# ArduinoFIO.net
KiCad netlist of a schematic drawn in Altium Designer
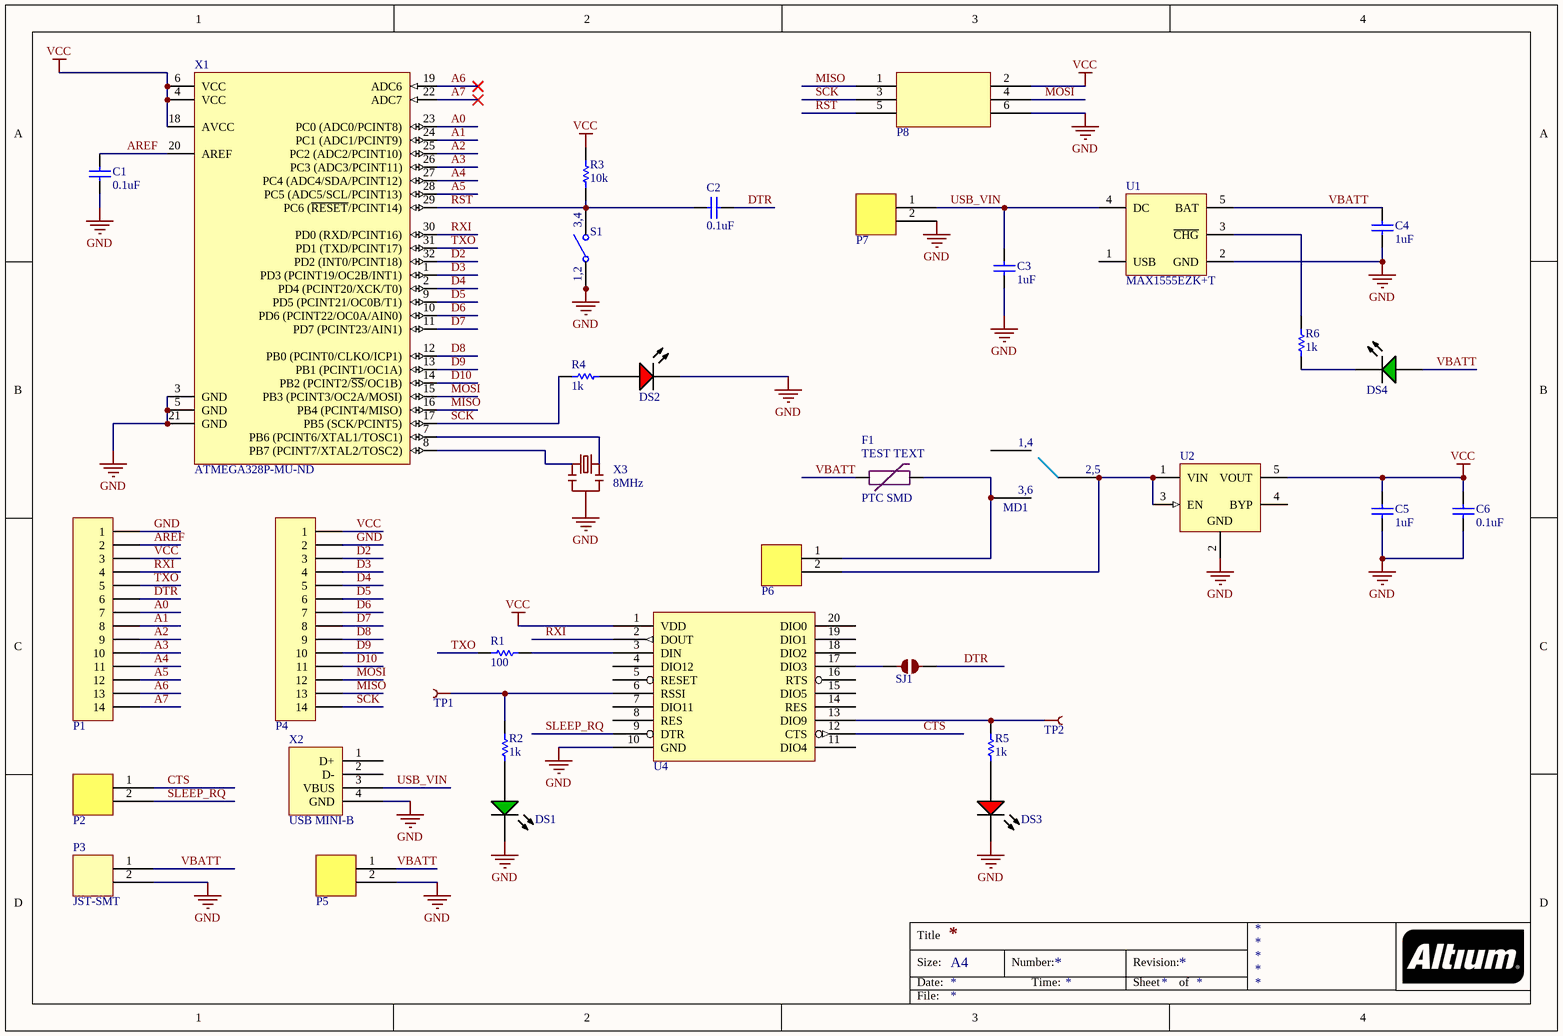
[diagram p0: ArduinoFIO.SchDoc]

(export (version "E")
  (design (tool "Eeschema 10.0.6"))
  (components
    (comp (ref "C1")
      (value "0.1uF")
      (footprint "Main PCB Library:0402")
      (description "CAP CER 0.1UF 50V 10% X7R 0402")
      (fields
        (field (name "MANUFACTURER") "TDK Corporation")
        (field (name "MANUFACTURER PART NUMBER") "C1005X7R1H104K050BB")
      )
      (libsource (lib "Main SCH Library") (part "C1005X7R1H104K050BB"))
    )
    (comp (ref "C2")
      (value "0.1uF")
      (footprint "Main PCB Library:0402")
      (description "CAP CER 0.1UF 50V 10% X7R 0402")
      (fields
        (field (name "MANUFACTURER") "TDK Corporation")
        (field (name "MANUFACTURER PART NUMBER") "C1005X7R1H104K050BB")
      )
      (libsource (lib "Main SCH Library") (part "C1005X7R1H104K050BB"))
    )
    (comp (ref "C3")
      (value "1uF")
      (footprint "Main PCB Library:0402")
      (description "CAP CER 1UF 6.3V 10% X5R 0402")
      (fields
        (field (name "MANUFACTURER") "Murata Electronics North America")
        (field (name "MANUFACTURER PART NUMBER") "GRM155R60J105KE19D")
      )
      (libsource (lib "Main SCH Library") (part "GRM155R60J105KE19D"))
    )
    (comp (ref "C4")
      (value "1uF")
      (footprint "Main PCB Library:0402")
      (description "CAP CER 1UF 6.3V 10% X5R 0402")
      (fields
        (field (name "MANUFACTURER") "Murata Electronics North America")
        (field (name "MANUFACTURER PART NUMBER") "GRM155R60J105KE19D")
      )
      (libsource (lib "Main SCH Library") (part "GRM155R60J105KE19D"))
    )
    (comp (ref "C5")
      (value "1uF")
      (footprint "Main PCB Library:0402")
      (description "CAP CER 1UF 6.3V 10% X5R 0402")
      (fields
        (field (name "MANUFACTURER") "Murata Electronics North America")
        (field (name "MANUFACTURER PART NUMBER") "GRM155R60J105KE19D")
      )
      (libsource (lib "Main SCH Library") (part "GRM155R60J105KE19D"))
    )
    (comp (ref "C6")
      (value "0.1uF")
      (footprint "Main PCB Library:0402")
      (description "CAP CER 0.1UF 50V 10% X7R 0402")
      (fields
        (field (name "MANUFACTURER") "TDK Corporation")
        (field (name "MANUFACTURER PART NUMBER") "C1005X7R1H104K050BB")
      )
      (libsource (lib "Main SCH Library") (part "C1005X7R1H104K050BB"))
    )
    (comp (ref "DS1")
      (value "LTST-C191KGKT")
      (footprint "Main PCB Library:KING-LED0603-25-GREEN_V")
      (description "LED GREEN CLEAR THIN 0603 SMD")
      (fields (field (name "MANUFACTURER") "Lite-On Inc."))
      (libsource (lib "Main SCH Library") (part "LTST-C191KGKT"))
    )
    (comp (ref "DS2")
      (value "LTST-C191KRKT")
      (footprint "Main PCB Library:KING-LED0603-25-RED_V")
      (description "LED SUPER RED CLR THIN 0603 SMD")
      (fields (field (name "MANUFACTURER") "Lite-On Inc."))
      (libsource (lib "Main SCH Library") (part "LTST-C191KRKT"))
    )
    (comp (ref "DS3")
      (value "LTST-C191KRKT")
      (footprint "Main PCB Library:KING-LED0603-25-RED_V")
      (description "LED SUPER RED CLR THIN 0603 SMD")
      (fields (field (name "MANUFACTURER") "Lite-On Inc."))
      (libsource (lib "Main SCH Library") (part "LTST-C191KRKT"))
    )
    (comp (ref "DS4")
      (value "LTST-C191KGKT")
      (footprint "Main PCB Library:KING-LED0603-25-GREEN_V")
      (description "LED GREEN CLEAR THIN 0603 SMD")
      (fields (field (name "MANUFACTURER") "Lite-On Inc."))
      (libsource (lib "Main SCH Library") (part "LTST-C191KGKT"))
    )
    (comp (ref "F1")
      (value "PTC SMD")
      (footprint "PTC-1206")
      (description "PTC RESTTBLE 0.10A 60V CHIP 1206")
      (fields
        (field (name "MANUFACTURER") "Bel Fuse Inc.")
        (field (name "MANUFACTURER PART NUMBER") "0ZCJ0010FF2E")
      )
      (libsource (lib "Main SCH Library") (part "0ZCJ0010FF2E"))
    )
    (comp (ref "MD1")
      (value "AYZ0202AGRLC")
      (footprint "Main PCB Library:DPDT SMD")
      (description "SWITCH SLIDE DPDT 100MA 12V")
      (fields (field (name "MANUFACTURER") "C&K Components"))
      (libsource (lib "Main SCH Library") (part "AYZ0202AGRLC"))
    )
    (comp (ref "P1")
      (value "95278-101A14LF")
      (footprint "Main PCB Library:1X14")
      (description "BERGSTIK Header 14POS .100\" DR SMT")
      (fields (field (name "MANUFACTURER") "FCI"))
      (libsource (lib "Main SCH Library") (part "95278-101A14LF"))
    )
    (comp (ref "P2")
      (value "961102-6404-AR")
      (footprint "Main PCB Library:1X02")
      (description "CONN HEADER VERT SGL 2POS GOLD")
      (fields (field (name "MANUFACTURER") "3M"))
      (libsource (lib "Main SCH Library") (part "961102-6404-AR"))
    )
    (comp (ref "P3")
      (value "JST-SMT")
      (footprint "S2B-PH")
      (description "CONN HEADER PH SIDE 2POS 2MM SMD")
      (fields
        (field (name "MANUFACTURER") "JST Sales America Inc.")
        (field (name "MANUFACTURER PART NUMBER") "S2B-PH-SM4-TB(LF)(SN)")
      )
      (libsource (lib "Main SCH Library") (part "S2B-PH-SM4-TB(LF)(SN)"))
    )
    (comp (ref "P4")
      (value "95278-101A14LF")
      (footprint "Main PCB Library:1X14")
      (description "BERGSTIK Header 14POS .100\" DR SMT")
      (fields (field (name "MANUFACTURER") "FCI"))
      (libsource (lib "Main SCH Library") (part "95278-101A14LF"))
    )
    (comp (ref "P5")
      (value "961102-6404-AR")
      (footprint "Main PCB Library:1X02")
      (description "CONN HEADER VERT SGL 2POS GOLD")
      (fields (field (name "MANUFACTURER") "3M"))
      (libsource (lib "Main SCH Library") (part "961102-6404-AR"))
    )
    (comp (ref "P6")
      (value "961102-6404-AR")
      (footprint "Main PCB Library:1X02")
      (description "CONN HEADER VERT SGL 2POS GOLD")
      (fields (field (name "MANUFACTURER") "3M"))
      (libsource (lib "Main SCH Library") (part "961102-6404-AR"))
    )
    (comp (ref "P7")
      (value "961102-6404-AR")
      (footprint "Main PCB Library:1X02")
      (description "CONN HEADER VERT SGL 2POS GOLD")
      (fields (field (name "MANUFACTURER") "3M"))
      (libsource (lib "Main SCH Library") (part "961102-6404-AR"))
    )
    (comp (ref "P8")
      (value "M20-9980346")
      (footprint "Main PCB Library:2X3")
      (description "DIL VERTICAL PC TAIL PIN HEADER")
      (fields (field (name "MANUFACTURER") "Harwin Inc."))
      (libsource (lib "Main SCH Library") (part "M20-9980346"))
    )
    (comp (ref "R1")
      (value "100")
      (footprint "Main PCB Library:J1-0603")
      (description "RES SMD 100 OHM 1% 1/10W 0603")
      (fields
        (field (name "MANUFACTURER") "Yageo")
        (field (name "MANUFACTURER PART NUMBER") "RC0603FR-07100RL")
      )
      (libsource (lib "Main SCH Library") (part "RC0603FR-07100RL"))
    )
    (comp (ref "R2")
      (value "1k")
      (footprint "Main PCB Library:J1-0603")
      (description "RES SMD 1K OHM 5% 1/10W 0603")
      (fields
        (field (name "MANUFACTURER") "Yageo")
        (field (name "MANUFACTURER PART NUMBER") "RC0603JR-071KL")
      )
      (libsource (lib "Main SCH Library") (part "RC0603JR-071KL"))
    )
    (comp (ref "R3")
      (value "10k")
      (footprint "Main PCB Library:J1-0603")
      (description "RES SMD 10K OHM 1% 1/10W 0603")
      (fields
        (field (name "MANUFACTURER") "Panasonic Electronic Components")
        (field (name "MANUFACTURER PART NUMBER") "ERJ-3EKF1002V")
      )
      (libsource (lib "Main SCH Library") (part "ERJ-3EKF1002V"))
    )
    (comp (ref "R4")
      (value "1k")
      (footprint "Main PCB Library:J1-0603")
      (description "RES SMD 1K OHM 5% 1/10W 0603")
      (fields
        (field (name "MANUFACTURER") "Yageo")
        (field (name "MANUFACTURER PART NUMBER") "RC0603JR-071KL")
      )
      (libsource (lib "Main SCH Library") (part "RC0603JR-071KL"))
    )
    (comp (ref "R5")
      (value "1k")
      (footprint "Main PCB Library:J1-0603")
      (description "RES SMD 1K OHM 5% 1/10W 0603")
      (fields
        (field (name "MANUFACTURER") "Yageo")
        (field (name "MANUFACTURER PART NUMBER") "RC0603JR-071KL")
      )
      (libsource (lib "Main SCH Library") (part "RC0603JR-071KL"))
    )
    (comp (ref "R6")
      (value "1k")
      (footprint "Main PCB Library:J1-0603")
      (description "RES SMD 1K OHM 5% 1/10W 0603")
      (fields
        (field (name "MANUFACTURER") "Yageo")
        (field (name "MANUFACTURER PART NUMBER") "RC0603JR-071KL")
      )
      (libsource (lib "Main SCH Library") (part "RC0603JR-071KL"))
    )
    (comp (ref "S1")
      (value "PTS645SH50SMTR92 LFS")
      (footprint "Main PCB Library:TACTILE SWITCH SMD")
      (description "SWITCH TACTILE SPST-NO 0.05A 12V")
      (fields (field (name "MANUFACTURER") "C&K Components"))
      (libsource (lib "Main SCH Library") (part "PTS645SH50SMTR92 LFS"))
    )
    (comp (ref "SJ1")
      (value "SOLDERJUMPERNC")
      (footprint "Main PCB Library:SJ_2S")
      (description "=SupplierDescription")
      (libsource (lib "Main SCH Library") (part "SOLDERJUMPERNC"))
    )
    (comp (ref "TP1")
      (value "TEST-POINT3X5")
      (footprint "Main PCB Library:PAD.03X.05")
      (description "=SupplierDescription")
      (libsource (lib "Main SCH Library") (part "TEST-POINT3X5"))
    )
    (comp (ref "TP2")
      (value "TEST-POINT3X5")
      (footprint "Main PCB Library:PAD.03X.05")
      (description "=SupplierDescription")
      (libsource (lib "") (part "TEST-POINT3X5_1"))
    )
    (comp (ref "U1")
      (value "MAX1555EZK+T")
      (footprint "Main PCB Library:SOT23-5")
      (description "IC BATT CHRGR LI+ 1CELL SOT23-5")
      (fields (field (name "MANUFACTURER") "Maxim Integrated"))
      (libsource (lib "Main SCH Library") (part "MAX1555EZK+T"))
    )
    (comp (ref "U2")
      (value "CAT6219-330TDGT3")
      (footprint "Main PCB Library:SOT23-5")
      (description "IC REG LDO 3.3V 0.5A TSOT23-5")
      (fields (field (name "MANUFACTURER") "ON Semiconductor"))
      (libsource (lib "Main SCH Library") (part "CAT6219-330TDGT3"))
    )
    (comp (ref "U4")
      (value "XB24-API-001")
      (footprint "Main PCB Library:XBEE-SMD")
      (description "MOD XBEE 802.15.4 1MW W/PCB ANT")
      (fields (field (name "MANUFACTURER") "Digi International"))
      (libsource (lib "Main SCH Library") (part "XB24-API-001"))
    )
    (comp (ref "X1")
      (value "ATMEGA328P-MU")
      (footprint "Main PCB Library:32A_N")
      (description "IC MCU 8BIT 32KB FLASH 32QFN")
      (fields
        (field (name "MANUFACTURER") "Atmel")
        (field (name "SUPPLIER PART NUMBER 1") "ATMEGA328P-MU-ND")
      )
      (libsource (lib "Main SCH Library") (part "ATMEGA328P-MU"))
    )
    (comp (ref "X2")
      (value "USB MINI-B")
      (footprint "Main PCB Library:USB-MINIB")
      (description "CONN MINI USB RCPT RA TYPE B SMD")
      (fields
        (field (name "MANUFACTURER") "FCI")
        (field (name "MANUFACTURER PART NUMBER") "10033526-N3212LF")
      )
      (libsource (lib "Main SCH Library") (part "10033526-N3212LF"))
    )
    (comp (ref "X3")
      (value "8MHz")
      (footprint "Main PCB Library:RESONATOR-SMD")
      (description "CER RESONATOR 10MHZ SMD")
      (fields
        (field (name "MANUFACTURER") "Murata Electronics North America")
        (field (name "MANUFACTURER PART NUMBER") "CSTCE10M0G55Z-R0")
      )
      (libsource (lib "Main SCH Library") (part "CSTCE10M0G55Z-R0"))
    )
  )
  (nets
    (net (code "1") (name "/A0") (class "Default")
      (node (ref "P1") (pin "7") (pinfunction "7_7") (pintype "passive"))
      (node (ref "X1") (pin "23") (pinfunction "PC0_(ADC0/PCINT8)_23") (pintype "bidirectional"))
    )
    (net (code "2") (name "/A1") (class "Default")
      (node (ref "P1") (pin "8") (pinfunction "8_8") (pintype "passive"))
      (node (ref "X1") (pin "24") (pinfunction "PC1_(ADC1/PCINT9)_24") (pintype "bidirectional"))
    )
    (net (code "3") (name "/A2") (class "Default")
      (node (ref "P1") (pin "9") (pinfunction "9_9") (pintype "passive"))
      (node (ref "X1") (pin "25") (pinfunction "PC2_(ADC2/PCINT10)_25") (pintype "bidirectional"))
    )
    (net (code "4") (name "/A3") (class "Default")
      (node (ref "P1") (pin "10") (pinfunction "10_10") (pintype "passive"))
      (node (ref "X1") (pin "26") (pinfunction "PC3_(ADC3/PCINT11)_26") (pintype "bidirectional"))
    )
    (net (code "5") (name "/A4") (class "Default")
      (node (ref "P1") (pin "11") (pinfunction "11_11") (pintype "passive"))
      (node (ref "X1") (pin "27") (pinfunction "PC4_(ADC4/SDA/PCINT12)_27") (pintype "bidirectional"))
    )
    (net (code "6") (name "/A5") (class "Default")
      (node (ref "P1") (pin "12") (pinfunction "12_12") (pintype "passive"))
      (node (ref "X1") (pin "28") (pinfunction "PC5_(ADC5/SCL/PCINT13)_28") (pintype "bidirectional"))
    )
    (net (code "7") (name "/A6") (class "Default")
      (node (ref "P1") (pin "13") (pinfunction "13_13") (pintype "passive"))
      (node (ref "X1") (pin "19") (pinfunction "ADC6_19") (pintype "input"))
    )
    (net (code "8") (name "/A7") (class "Default")
      (node (ref "P1") (pin "14") (pinfunction "14_14") (pintype "passive"))
      (node (ref "X1") (pin "22") (pinfunction "ADC7_22") (pintype "input"))
    )
    (net (code "9") (name "/AREF") (class "Default")
      (node (ref "C1") (pin "2") (pinfunction "2_2") (pintype "passive"))
      (node (ref "P1") (pin "2") (pinfunction "2_2") (pintype "passive"))
      (node (ref "X1") (pin "20") (pinfunction "AREF_20") (pintype "passive"))
    )
    (net (code "10") (name "/CTS") (class "Default")
      (node (ref "P2") (pin "1") (pinfunction "1_1") (pintype "passive"))
      (node (ref "U4") (pin "12") (pinfunction "CTS_12") (pintype "output"))
    )
    (net (code "11") (name "/D2") (class "Default")
      (node (ref "P4") (pin "3") (pinfunction "3_3") (pintype "passive"))
      (node (ref "X1") (pin "32") (pinfunction "PD2_(INT0/PCINT18)_32") (pintype "bidirectional"))
    )
    (net (code "12") (name "/D3") (class "Default")
      (node (ref "P4") (pin "4") (pinfunction "4_4") (pintype "passive"))
      (node (ref "X1") (pin "1") (pinfunction "PD3_(PCINT19/OC2B/INT1)_1") (pintype "bidirectional"))
    )
    (net (code "13") (name "/D4") (class "Default")
      (node (ref "P4") (pin "5") (pinfunction "5_5") (pintype "passive"))
      (node (ref "X1") (pin "2") (pinfunction "PD4_(PCINT20/XCK/T0)_2") (pintype "bidirectional"))
    )
    (net (code "14") (name "/D5") (class "Default")
      (node (ref "P4") (pin "6") (pinfunction "6_6") (pintype "passive"))
      (node (ref "X1") (pin "9") (pinfunction "PD5_(PCINT21/OC0B/T1)_9") (pintype "bidirectional"))
    )
    (net (code "15") (name "/D6") (class "Default")
      (node (ref "P4") (pin "7") (pinfunction "7_7") (pintype "passive"))
      (node (ref "X1") (pin "10") (pinfunction "PD6_(PCINT22/OC0A/AIN0)_10") (pintype "bidirectional"))
    )
    (net (code "16") (name "/D7") (class "Default")
      (node (ref "P4") (pin "8") (pinfunction "8_8") (pintype "passive"))
      (node (ref "X1") (pin "11") (pinfunction "PD7_(PCINT23/AIN1)_11") (pintype "bidirectional"))
    )
    (net (code "17") (name "/D8") (class "Default")
      (node (ref "P4") (pin "9") (pinfunction "9_9") (pintype "passive"))
      (node (ref "X1") (pin "12") (pinfunction "PB0_(PCINT0/CLKO/ICP1)_12") (pintype "bidirectional"))
    )
    (net (code "18") (name "/D9") (class "Default")
      (node (ref "P4") (pin "10") (pinfunction "10_10") (pintype "passive"))
      (node (ref "X1") (pin "13") (pinfunction "PB1_(PCINT1/OC1A)_13") (pintype "bidirectional"))
    )
    (net (code "19") (name "/D10") (class "Default")
      (node (ref "P4") (pin "11") (pinfunction "11_11") (pintype "passive"))
      (node (ref "X1") (pin "14") (pinfunction "PB2_(PCINT2/~{SS}/OC1B)_14") (pintype "bidirectional"))
    )
    (net (code "20") (name "/DTR") (class "Default")
      (node (ref "C2") (pin "2") (pinfunction "2_2") (pintype "passive"))
      (node (ref "P1") (pin "6") (pinfunction "6_6") (pintype "passive"))
      (node (ref "SJ1") (pin "2") (pinfunction "2_2") (pintype "passive"))
    )
    (net (code "21") (name "/MISO") (class "Default")
      (node (ref "P4") (pin "13") (pinfunction "13_13") (pintype "passive"))
      (node (ref "P8") (pin "1") (pintype "passive"))
      (node (ref "X1") (pin "16") (pinfunction "PB4_(PCINT4/MISO)_16") (pintype "bidirectional"))
    )
    (net (code "22") (name "/MOSI") (class "Default")
      (node (ref "P4") (pin "12") (pinfunction "12_12") (pintype "passive"))
      (node (ref "P8") (pin "4") (pintype "passive"))
      (node (ref "X1") (pin "15") (pinfunction "PB3_(PCINT3/OC2A/MOSI)_15") (pintype "bidirectional"))
    )
    (net (code "23") (name "/RST") (class "Default")
      (node (ref "C2") (pin "1") (pinfunction "1_1") (pintype "passive"))
      (node (ref "P8") (pin "5") (pintype "passive"))
      (node (ref "R3") (pin "1") (pinfunction "1_1") (pintype "passive"))
      (node (ref "S1") (pin "3") (pinfunction "3_3") (pintype "passive"))
      (node (ref "S1") (pin "4") (pinfunction "4_4") (pintype "passive"))
      (node (ref "X1") (pin "29") (pinfunction "PC6_(~{RESET}/PCINT14)_29") (pintype "bidirectional"))
    )
    (net (code "24") (name "/RXI") (class "Default")
      (node (ref "P1") (pin "4") (pinfunction "4_4") (pintype "passive"))
      (node (ref "U4") (pin "2") (pinfunction "DOUT_2") (pintype "output"))
      (node (ref "X1") (pin "30") (pinfunction "PD0_(RXD/PCINT16)_30") (pintype "bidirectional"))
    )
    (net (code "25") (name "/SCK") (class "Default")
      (node (ref "P4") (pin "14") (pinfunction "14_14") (pintype "passive"))
      (node (ref "P8") (pin "3") (pintype "passive"))
      (node (ref "R4") (pin "1") (pinfunction "1_1") (pintype "passive"))
      (node (ref "X1") (pin "17") (pinfunction "PB5_(SCK/PCINT5)_17") (pintype "bidirectional"))
    )
    (net (code "26") (name "/SLEEP_RQ") (class "Default")
      (node (ref "P2") (pin "2") (pinfunction "2_2") (pintype "passive"))
      (node (ref "U4") (pin "9") (pinfunction "DTR_9") (pintype "passive"))
    )
    (net (code "27") (name "/TXO") (class "Default")
      (node (ref "P1") (pin "5") (pinfunction "5_5") (pintype "passive"))
      (node (ref "R1") (pin "1") (pinfunction "1_1") (pintype "passive"))
      (node (ref "X1") (pin "31") (pinfunction "PD1_(TXD/PCINT17)_31") (pintype "bidirectional"))
    )
    (net (code "28") (name "/USB_VIN") (class "Default")
      (node (ref "C3") (pin "2") (pinfunction "2_2") (pintype "passive"))
      (node (ref "P7") (pin "1") (pinfunction "1_1") (pintype "passive"))
      (node (ref "U1") (pin "4") (pinfunction "DC_4") (pintype "power_in"))
      (node (ref "X2") (pin "3") (pinfunction "VBUS_3") (pintype "passive"))
    )
    (net (code "29") (name "/VBATT") (class "Default")
      (node (ref "C4") (pin "2") (pinfunction "2_2") (pintype "passive"))
      (node (ref "DS4") (pin "1") (pinfunction "A_1") (pintype "passive"))
      (node (ref "F1") (pin "1") (pinfunction "1_1") (pintype "passive"))
      (node (ref "P3") (pin "1") (pinfunction "1_1") (pintype "passive"))
      (node (ref "P5") (pin "1") (pinfunction "1_1") (pintype "passive"))
      (node (ref "U1") (pin "5") (pinfunction "BAT_5") (pintype "power_in"))
    )
    (net (code "30") (name "GND") (class "Default")
      (node (ref "C1") (pin "1") (pinfunction "1_1") (pintype "passive"))
      (node (ref "C3") (pin "1") (pinfunction "1_1") (pintype "passive"))
      (node (ref "C4") (pin "1") (pinfunction "1_1") (pintype "passive"))
      (node (ref "C5") (pin "1") (pinfunction "1_1") (pintype "passive"))
      (node (ref "C6") (pin "1") (pinfunction "1_1") (pintype "passive"))
      (node (ref "DS1") (pin "2") (pinfunction "K_2") (pintype "passive"))
      (node (ref "DS2") (pin "2") (pinfunction "K_2") (pintype "passive"))
      (node (ref "DS3") (pin "2") (pinfunction "K_2") (pintype "passive"))
      (node (ref "P1") (pin "1") (pinfunction "1_1") (pintype "passive"))
      (node (ref "P3") (pin "2") (pinfunction "2_2") (pintype "passive"))
      (node (ref "P4") (pin "2") (pinfunction "2_2") (pintype "passive"))
      (node (ref "P5") (pin "2") (pinfunction "2_2") (pintype "passive"))
      (node (ref "P7") (pin "2") (pinfunction "2_2") (pintype "passive"))
      (node (ref "P8") (pin "6") (pintype "passive"))
      (node (ref "S1") (pin "1") (pinfunction "1_1") (pintype "passive"))
      (node (ref "S1") (pin "2") (pinfunction "2_2") (pintype "passive"))
      (node (ref "U1") (pin "2") (pinfunction "GND_2") (pintype "power_in"))
      (node (ref "U2") (pin "2") (pinfunction "GND_2") (pintype "power_in"))
      (node (ref "U4") (pin "10") (pinfunction "GND_10") (pintype "passive"))
      (node (ref "X1") (pin "21") (pinfunction "GND_21") (pintype "power_in"))
      (node (ref "X1") (pin "3") (pinfunction "GND_3") (pintype "power_in"))
      (node (ref "X1") (pin "5") (pinfunction "GND_5") (pintype "power_in"))
      (node (ref "X2") (pin "4") (pinfunction "GND_4") (pintype "passive"))
      (node (ref "X3") (pin "2") (pinfunction "2_2") (pintype "passive"))
    )
    (net (code "31") (name "Net-(DS1-A)") (class "Default")
      (node (ref "DS1") (pin "1") (pinfunction "A_1") (pintype "passive"))
      (node (ref "R2") (pin "1") (pinfunction "1_1") (pintype "passive"))
    )
    (net (code "32") (name "Net-(DS2-A)") (class "Default")
      (node (ref "DS2") (pin "1") (pinfunction "A_1") (pintype "passive"))
      (node (ref "R4") (pin "2") (pinfunction "2_2") (pintype "passive"))
    )
    (net (code "33") (name "Net-(DS3-A)") (class "Default")
      (node (ref "DS3") (pin "1") (pinfunction "A_1") (pintype "passive"))
      (node (ref "R5") (pin "1") (pinfunction "1_1") (pintype "passive"))
    )
    (net (code "34") (name "Net-(DS4-K)") (class "Default")
      (node (ref "DS4") (pin "2") (pinfunction "K_2") (pintype "passive"))
      (node (ref "R6") (pin "1") (pinfunction "1_1") (pintype "passive"))
    )
    (net (code "35") (name "Net-(F1-Pad2)") (class "Default")
      (node (ref "F1") (pin "2") (pinfunction "2_2") (pintype "passive"))
      (node (ref "MD1") (pin "3") (pinfunction "3_3") (pintype "passive"))
      (node (ref "MD1") (pin "6") (pinfunction "6_6") (pintype "passive"))
      (node (ref "P6") (pin "1") (pinfunction "1_1") (pintype "passive"))
    )
    (net (code "36") (name "Net-(MD1-Pad1)") (class "Default")
      (node (ref "MD1") (pin "1") (pinfunction "1_1") (pintype "passive"))
      (node (ref "MD1") (pin "4") (pinfunction "4_4") (pintype "passive"))
    )
    (net (code "37") (name "Net-(U1-~{CHG})") (class "Default")
      (node (ref "R6") (pin "2") (pinfunction "2_2") (pintype "passive"))
      (node (ref "U1") (pin "3") (pinfunction "~{CHG}_3") (pintype "tri_state"))
    )
    (net (code "38") (name "Net-(U2-EN)") (class "Default")
      (node (ref "MD1") (pin "2") (pinfunction "2_2") (pintype "passive"))
      (node (ref "MD1") (pin "5") (pinfunction "5_5") (pintype "passive"))
      (node (ref "P6") (pin "2") (pinfunction "2_2") (pintype "passive"))
      (node (ref "U2") (pin "1") (pinfunction "VIN_1") (pintype "power_in"))
      (node (ref "U2") (pin "3") (pinfunction "EN_3") (pintype "input"))
    )
    (net (code "39") (name "Net-(U4-DIN)") (class "Default")
      (node (ref "R1") (pin "2") (pinfunction "2_2") (pintype "passive"))
      (node (ref "U4") (pin "3") (pinfunction "DIN_3") (pintype "passive"))
    )
    (net (code "40") (name "Net-(U4-DIO3)") (class "Default")
      (node (ref "SJ1") (pin "1") (pinfunction "1_1") (pintype "passive"))
      (node (ref "U4") (pin "17") (pinfunction "DIO3_17") (pintype "passive"))
    )
    (net (code "41") (name "Net-(U4-DIO9)") (class "Default")
      (node (ref "R5") (pin "2") (pinfunction "2_2") (pintype "passive"))
      (node (ref "TP2") (pin "1") (pinfunction "1_1") (pintype "passive"))
      (node (ref "U4") (pin "13") (pinfunction "DIO9_13") (pintype "passive"))
    )
    (net (code "42") (name "Net-(U4-RSSI)") (class "Default")
      (node (ref "R2") (pin "2") (pinfunction "2_2") (pintype "passive"))
      (node (ref "TP1") (pin "1") (pinfunction "1_1") (pintype "passive"))
      (node (ref "U4") (pin "6") (pinfunction "RSSI_6") (pintype "passive"))
    )
    (net (code "43") (name "Net-(X1-PB6_(PCINT6{slash}XTAL1{slash}TOSC1))") (class "Default")
      (node (ref "X1") (pin "7") (pinfunction "PB6_(PCINT6/XTAL1/TOSC1)_7") (pintype "bidirectional"))
      (node (ref "X3") (pin "1") (pinfunction "1_1") (pintype "passive"))
    )
    (net (code "44") (name "Net-(X1-PB7_(PCINT7{slash}XTAL2{slash}TOSC2))") (class "Default")
      (node (ref "X1") (pin "8") (pinfunction "PB7_(PCINT7/XTAL2/TOSC2)_8") (pintype "bidirectional"))
      (node (ref "X3") (pin "3") (pinfunction "3_3") (pintype "passive"))
    )
    (net (code "45") (name "VCC") (class "Default")
      (node (ref "C5") (pin "2") (pinfunction "2_2") (pintype "passive"))
      (node (ref "C6") (pin "2") (pinfunction "2_2") (pintype "passive"))
      (node (ref "P1") (pin "3") (pinfunction "3_3") (pintype "passive"))
      (node (ref "P4") (pin "1") (pinfunction "1_1") (pintype "passive"))
      (node (ref "P8") (pin "2") (pintype "passive"))
      (node (ref "R3") (pin "2") (pinfunction "2_2") (pintype "passive"))
      (node (ref "U2") (pin "5") (pinfunction "VOUT_5") (pintype "power_in"))
      (node (ref "U4") (pin "1") (pinfunction "VDD_1") (pintype "passive"))
      (node (ref "X1") (pin "18") (pinfunction "AVCC_18") (pintype "power_in"))
      (node (ref "X1") (pin "4") (pinfunction "VCC_4") (pintype "power_in"))
      (node (ref "X1") (pin "6") (pinfunction "VCC_6") (pintype "power_in"))
    )
    (net (code "46") (name "unconnected-(U1-USB-Pad1)") (class "Default")
      (node (ref "U1") (pin "1") (pinfunction "USB_1") (pintype "power_in"))
    )
    (net (code "47") (name "unconnected-(U2-BYP-Pad4)") (class "Default")
      (node (ref "U2") (pin "4") (pinfunction "BYP_4") (pintype "passive"))
    )
    (net (code "48") (name "unconnected-(U4-DIO0-Pad20)") (class "Default")
      (node (ref "U4") (pin "20") (pinfunction "DIO0_20") (pintype "passive"))
    )
    (net (code "49") (name "unconnected-(U4-DIO1-Pad19)") (class "Default")
      (node (ref "U4") (pin "19") (pinfunction "DIO1_19") (pintype "passive"))
    )
    (net (code "50") (name "unconnected-(U4-DIO2-Pad18)") (class "Default")
      (node (ref "U4") (pin "18") (pinfunction "DIO2_18") (pintype "passive"))
    )
    (net (code "51") (name "unconnected-(U4-DIO4-Pad11)") (class "Default")
      (node (ref "U4") (pin "11") (pinfunction "DIO4_11") (pintype "passive"))
    )
    (net (code "52") (name "unconnected-(U4-DIO5-Pad15)") (class "Default")
      (node (ref "U4") (pin "15") (pinfunction "DIO5_15") (pintype "passive"))
    )
    (net (code "53") (name "unconnected-(U4-DIO11-Pad7)") (class "Default")
      (node (ref "U4") (pin "7") (pinfunction "DIO11_7") (pintype "passive"))
    )
    (net (code "54") (name "unconnected-(U4-DIO12-Pad4)") (class "Default")
      (node (ref "U4") (pin "4") (pinfunction "DIO12_4") (pintype "passive"))
    )
    (net (code "55") (name "unconnected-(U4-RES-Pad8)") (class "Default")
      (node (ref "U4") (pin "8") (pinfunction "RES_8") (pintype "passive"))
    )
    (net (code "56") (name "unconnected-(U4-RES-Pad14)") (class "Default")
      (node (ref "U4") (pin "14") (pinfunction "RES_14") (pintype "passive"))
    )
    (net (code "57") (name "unconnected-(U4-RESET-Pad5)") (class "Default")
      (node (ref "U4") (pin "5") (pinfunction "RESET_5") (pintype "passive"))
    )
    (net (code "58") (name "unconnected-(U4-RTS-Pad16)") (class "Default")
      (node (ref "U4") (pin "16") (pinfunction "RTS_16") (pintype "passive"))
    )
    (net (code "59") (name "unconnected-(X2-D+-Pad1)") (class "Default")
      (node (ref "X2") (pin "1") (pinfunction "D+_1") (pintype "passive"))
    )
    (net (code "60") (name "unconnected-(X2-D--Pad2)") (class "Default")
      (node (ref "X2") (pin "2") (pinfunction "D-_2") (pintype "passive"))
    )
  )
)
